# 7688A-kit-V2-1.net
KiCad netlist of a schematic drawn in Altium Designer
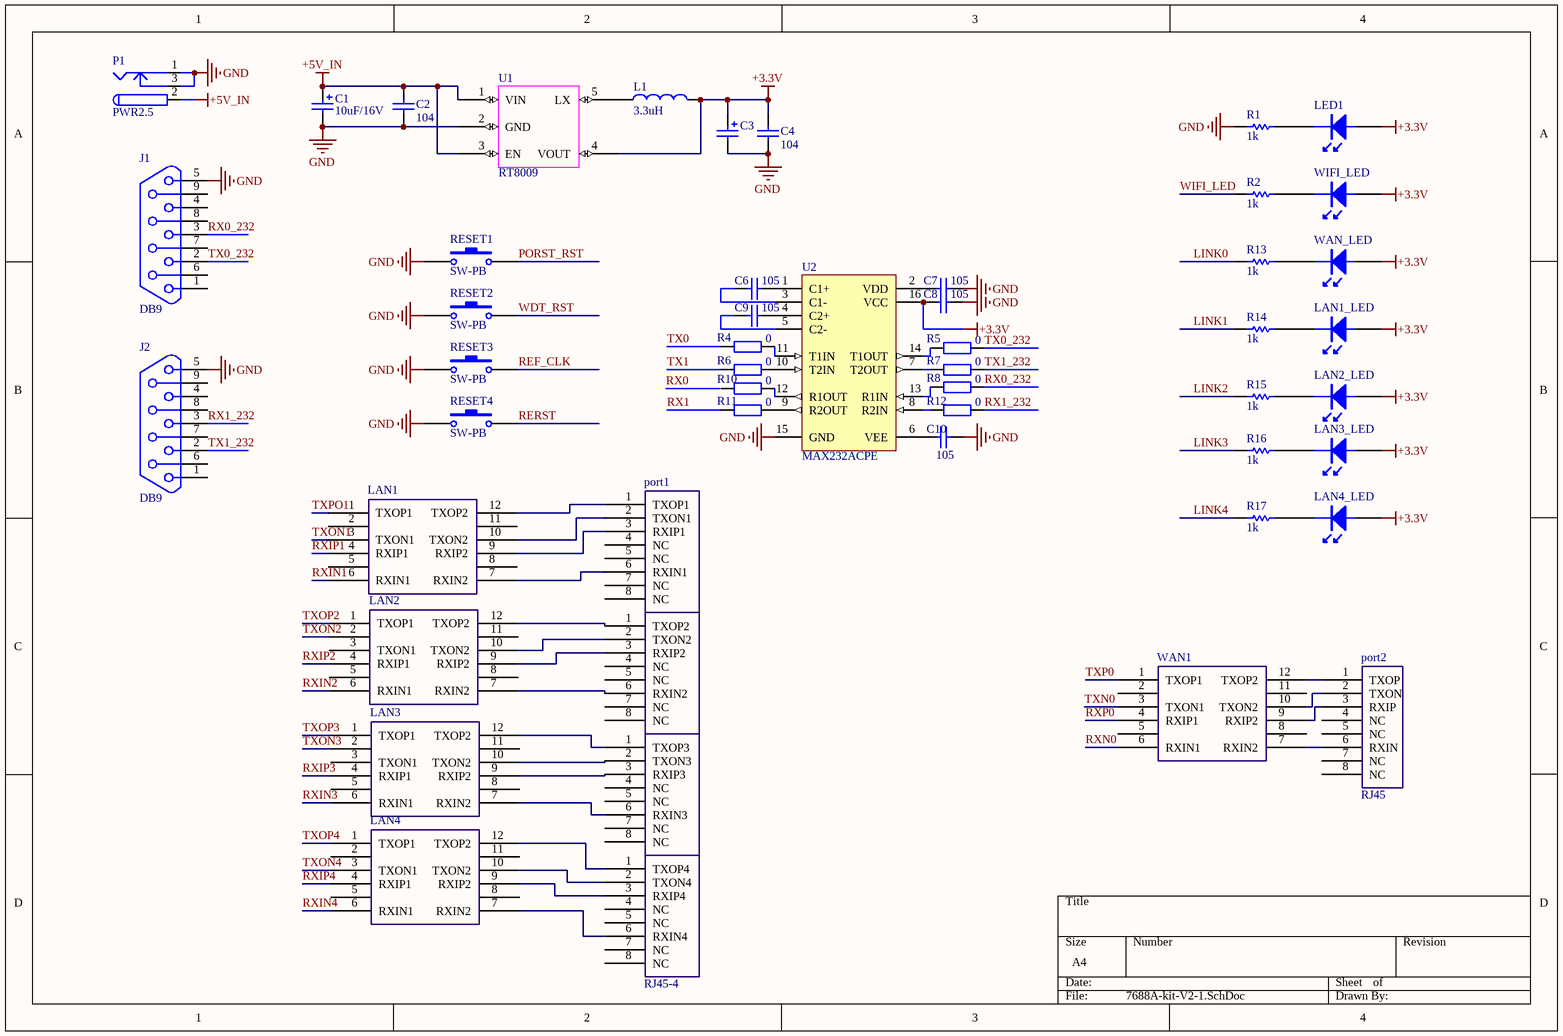
[diagram p0: 7688A-kit-V2-1.SchDoc]

(export (version "E")
  (design (tool "Eeschema 10.0.6"))
  (components
    (comp (ref "C1")
      (value "10uF/16V")
      (footprint "0805")
      (description "Polarized Capacitor (Surface Mount)")
      (fields
        (field (name "MANUFACTURER") "Generic Components")
        (field (name "PUBLISHER") "Altium Hobart Technology Centre")
      )
      (libsource (lib "*") (part "Cap Pol3"))
    )
    (comp (ref "C2")
      (value "104")
      (footprint "0603")
      (description "Capacitor")
      (fields
        (field (name "MANUFACTURER") "Generic Components")
        (field (name "PUBLISHER") "Altium Hobart Technology Centre")
      )
      (libsource (lib "*") (part "Cap"))
    )
    (comp (ref "C3")
      (value "10uF/16V")
      (footprint "0805")
      (description "Polarized Capacitor (Surface Mount)")
      (fields
        (field (name "MANUFACTURER") "Generic Components")
        (field (name "PUBLISHER") "Altium Hobart Technology Centre")
      )
      (libsource (lib "*") (part "Cap Pol3"))
    )
    (comp (ref "C4")
      (value "104")
      (footprint "0603")
      (description "Capacitor")
      (fields
        (field (name "MANUFACTURER") "Generic Components")
        (field (name "PUBLISHER") "Altium Hobart Technology Centre")
      )
      (libsource (lib "*") (part "Cap"))
    )
    (comp (ref "C6")
      (value "105")
      (footprint "0603")
      (description "Capacitor")
      (fields (field (name "PUBLISHER") "Altium Limited"))
      (libsource (lib "HLK-RM04_KIT-V2.3") (part "Cap"))
    )
    (comp (ref "C7")
      (value "105")
      (footprint "0603")
      (description "Capacitor")
      (fields (field (name "PUBLISHER") "Altium Limited"))
      (libsource (lib "HLK-RM04_KIT-V2.3") (part "Cap"))
    )
    (comp (ref "C8")
      (value "105")
      (footprint "0603")
      (description "Capacitor")
      (fields (field (name "PUBLISHER") "Altium Limited"))
      (libsource (lib "HLK-RM04_KIT-V2.3") (part "Cap"))
    )
    (comp (ref "C9")
      (value "105")
      (footprint "0603")
      (description "Capacitor")
      (fields (field (name "PUBLISHER") "Altium Limited"))
      (libsource (lib "HLK-RM04_KIT-V2.3") (part "Cap"))
    )
    (comp (ref "C10")
      (value "105")
      (footprint "0603")
      (description "Capacitor")
      (fields (field (name "PUBLISHER") "Altium Limited"))
      (libsource (lib "HLK-RM04_KIT-V2.3") (part "Cap"))
    )
    (comp (ref "J1") (value "DB9") (footprint "DB9s") (libsource (lib "HLK-RM04_KIT-V2.3") (part "DB9")))
    (comp (ref "J2") (value "DB9") (footprint "DB9s") (libsource (lib "HLK-RM04_KIT-V2.3") (part "DB9")))
    (comp (ref "L1") (value "3.3uH") (footprint "2520") (libsource (lib "ARM9") (part "INDUCTOR1")))
    (comp (ref "LAN1") (value "~") (footprint "tf-1016dg") (libsource (lib "TF-1016DG") (part "Component_1")))
    (comp (ref "LAN1_LED")
      (value "~")
      (footprint "0603LED")
      (libsource (lib "Miscellaneous Devices") (part "LED"))
    )
    (comp (ref "LAN2") (value "~") (footprint "tf-1016dg") (libsource (lib "TF-1016DG") (part "Component_1")))
    (comp (ref "LAN2_LED")
      (value "~")
      (footprint "0603LED")
      (libsource (lib "Miscellaneous Devices") (part "LED"))
    )
    (comp (ref "LAN3") (value "~") (footprint "tf-1016dg") (libsource (lib "TF-1016DG") (part "Component_1")))
    (comp (ref "LAN3_LED")
      (value "~")
      (footprint "0603LED")
      (libsource (lib "Miscellaneous Devices") (part "LED"))
    )
    (comp (ref "LAN4") (value "~") (footprint "tf-1016dg") (libsource (lib "TF-1016DG") (part "Component_1")))
    (comp (ref "LAN4_LED")
      (value "~")
      (footprint "0603LED")
      (libsource (lib "Miscellaneous Devices") (part "LED"))
    )
    (comp (ref "LED1")
      (value "~")
      (footprint "0603LED")
      (libsource (lib "Miscellaneous Devices") (part "LED"))
    )
    (comp (ref "P1")
      (value "PWR2.5")
      (footprint "HLK-M35-KIT-V2.1:POWER_STK1")
      (description "Low Voltage Power Supply Connector")
      (libsource (lib "HLK-RM04_KIT-V2.3") (part "PWR2.5"))
    )
    (comp (ref "port1") (value "RJ45-4") (footprint "RJ45-4") (libsource (lib "TF-1016DG") (part "RJ45-4")))
    (comp (ref "port2") (value "RJ45") (footprint "RJ45-8P8C") (libsource (lib "TF-1016DG") (part "RJ45")))
    (comp (ref "R1")
      (value "1k")
      (footprint "0603")
      (description "Resistor")
      (fields (field (name "Comment") "Res1") (field (name "PUBLISHER") "Altium Limited"))
      (libsource (lib "Miscellaneous Devices") (part "Res1"))
    )
    (comp (ref "R2")
      (value "1k")
      (footprint "0603")
      (description "Resistor")
      (fields (field (name "Comment") "Res1") (field (name "PUBLISHER") "Altium Limited"))
      (libsource (lib "Miscellaneous Devices") (part "Res1"))
    )
    (comp (ref "R4")
      (value "0")
      (footprint "0603")
      (description "Resistor")
      (fields (field (name "PUBLISHER") "Altium Limited"))
      (libsource (lib "HLK-RM04_KIT-V2.3") (part "Res2"))
    )
    (comp (ref "R5")
      (value "0")
      (footprint "0603")
      (description "Resistor")
      (fields (field (name "PUBLISHER") "Altium Limited"))
      (libsource (lib "HLK-RM04_KIT-V2.3") (part "Res2"))
    )
    (comp (ref "R6")
      (value "0")
      (footprint "0603")
      (description "Resistor")
      (fields (field (name "PUBLISHER") "Altium Limited"))
      (libsource (lib "HLK-RM04_KIT-V2.3") (part "Res2"))
    )
    (comp (ref "R7")
      (value "0")
      (footprint "0603")
      (description "Resistor")
      (fields (field (name "PUBLISHER") "Altium Limited"))
      (libsource (lib "HLK-RM04_KIT-V2.3") (part "Res2"))
    )
    (comp (ref "R8")
      (value "0")
      (footprint "0603")
      (description "Resistor")
      (fields (field (name "PUBLISHER") "Altium Limited"))
      (libsource (lib "HLK-RM04_KIT-V2.3") (part "Res2"))
    )
    (comp (ref "R10")
      (value "0")
      (footprint "0603")
      (description "Resistor")
      (fields (field (name "PUBLISHER") "Altium Limited"))
      (libsource (lib "HLK-RM04_KIT-V2.3") (part "Res2"))
    )
    (comp (ref "R11")
      (value "0")
      (footprint "0603")
      (description "Resistor")
      (fields (field (name "PUBLISHER") "Altium Limited"))
      (libsource (lib "HLK-RM04_KIT-V2.3") (part "Res2"))
    )
    (comp (ref "R12")
      (value "0")
      (footprint "0603")
      (description "Resistor")
      (fields (field (name "PUBLISHER") "Altium Limited"))
      (libsource (lib "HLK-RM04_KIT-V2.3") (part "Res2"))
    )
    (comp (ref "R13")
      (value "1k")
      (footprint "0603")
      (description "Resistor")
      (fields (field (name "Comment") "Res1") (field (name "PUBLISHER") "Altium Limited"))
      (libsource (lib "Miscellaneous Devices") (part "Res1"))
    )
    (comp (ref "R14")
      (value "1k")
      (footprint "0603")
      (description "Resistor")
      (fields (field (name "Comment") "Res1") (field (name "PUBLISHER") "Altium Limited"))
      (libsource (lib "Miscellaneous Devices") (part "Res1"))
    )
    (comp (ref "R15")
      (value "1k")
      (footprint "0603")
      (description "Resistor")
      (fields (field (name "Comment") "Res1") (field (name "PUBLISHER") "Altium Limited"))
      (libsource (lib "Miscellaneous Devices") (part "Res1"))
    )
    (comp (ref "R16")
      (value "1k")
      (footprint "0603")
      (description "Resistor")
      (fields (field (name "Comment") "Res1") (field (name "PUBLISHER") "Altium Limited"))
      (libsource (lib "Miscellaneous Devices") (part "Res1"))
    )
    (comp (ref "R17")
      (value "1k")
      (footprint "0603")
      (description "Resistor")
      (fields (field (name "Comment") "Res1") (field (name "PUBLISHER") "Altium Limited"))
      (libsource (lib "Miscellaneous Devices") (part "Res1"))
    )
    (comp (ref "RESET1")
      (value "SW-PB")
      (footprint "SWITCH")
      (description "Switch")
      (fields (field (name "PUBLISHER") "Altium Limited"))
      (libsource (lib "Miscellaneous Devices") (part "SW-PB"))
    )
    (comp (ref "RESET2")
      (value "SW-PB")
      (footprint "SWITCH")
      (description "Switch")
      (fields (field (name "PUBLISHER") "Altium Limited"))
      (libsource (lib "Miscellaneous Devices") (part "SW-PB"))
    )
    (comp (ref "RESET3")
      (value "SW-PB")
      (footprint "SWITCH")
      (description "Switch")
      (fields (field (name "PUBLISHER") "Altium Limited"))
      (libsource (lib "Miscellaneous Devices") (part "SW-PB"))
    )
    (comp (ref "RESET4")
      (value "SW-PB")
      (footprint "SWITCH")
      (description "Switch")
      (fields (field (name "PUBLISHER") "Altium Limited"))
      (libsource (lib "Miscellaneous Devices") (part "SW-PB"))
    )
    (comp (ref "U1")
      (value "RT8009")
      (footprint "HLK-M35-KIT-V2.1:SOT23-5")
      (libsource (lib "ARM9") (part "RT8009"))
    )
    (comp (ref "U2")
      (value "MAX232ACPE")
      (footprint "HLK-M35-KIT-V2.1:MAX3232")
      (description "+5V Powered, Multi-Channel RS-232 Driver/Receiver")
      (fields (field (name "PUBLISHER") "Altium Limited"))
      (libsource (lib "HLK-RM04_KIT-V2.3") (part "MAX232ACPE"))
    )
    (comp (ref "WAN1") (value "~") (footprint "tf-1016dg") (libsource (lib "TF-1016DG") (part "Component_1")))
    (comp (ref "WAN_LED")
      (value "~")
      (footprint "0603LED")
      (libsource (lib "Miscellaneous Devices") (part "LED"))
    )
    (comp (ref "WIFI_LED")
      (value "~")
      (footprint "0603LED")
      (libsource (lib "Miscellaneous Devices") (part "LED"))
    )
  )
  (nets
    (net (code "1") (name "+3.3V") (class "Default")
      (node (ref "C3") (pin "1") (pinfunction "1_1") (pintype "passive"))
      (node (ref "C4") (pin "2") (pinfunction "2_2") (pintype "passive"))
      (node (ref "C8") (pin "1") (pinfunction "1_1") (pintype "passive"))
      (node (ref "L1") (pin "2") (pinfunction "2_2") (pintype "passive"))
      (node (ref "LAN1_LED") (pin "1") (pinfunction "1_1") (pintype "passive"))
      (node (ref "LAN2_LED") (pin "1") (pinfunction "1_1") (pintype "passive"))
      (node (ref "LAN3_LED") (pin "1") (pinfunction "1_1") (pintype "passive"))
      (node (ref "LAN4_LED") (pin "1") (pinfunction "1_1") (pintype "passive"))
      (node (ref "LED1") (pin "1") (pinfunction "1_1") (pintype "passive"))
      (node (ref "U1") (pin "4") (pinfunction "VOUT_4") (pintype "bidirectional"))
      (node (ref "U2") (pin "16") (pinfunction "VCC_16") (pintype "power_in"))
      (node (ref "WAN_LED") (pin "1") (pinfunction "1_1") (pintype "passive"))
      (node (ref "WIFI_LED") (pin "1") (pinfunction "1_1") (pintype "passive"))
    )
    (net (code "2") (name "+5V_IN") (class "Default")
      (node (ref "C1") (pin "1") (pinfunction "1_1") (pintype "passive"))
      (node (ref "C2") (pin "2") (pinfunction "2_2") (pintype "passive"))
      (node (ref "P1") (pin "2") (pinfunction "2_2") (pintype "power_in"))
      (node (ref "U1") (pin "1") (pinfunction "VIN_1") (pintype "bidirectional"))
      (node (ref "U1") (pin "3") (pinfunction "EN_3") (pintype "bidirectional"))
    )
    (net (code "3") (name "/LINK0") (class "Default")
      (node (ref "R13") (pin "2") (pinfunction "2_2") (pintype "passive"))
    )
    (net (code "4") (name "/LINK1") (class "Default")
      (node (ref "R14") (pin "2") (pinfunction "2_2") (pintype "passive"))
    )
    (net (code "5") (name "/LINK2") (class "Default")
      (node (ref "R15") (pin "2") (pinfunction "2_2") (pintype "passive"))
    )
    (net (code "6") (name "/LINK3") (class "Default")
      (node (ref "R16") (pin "2") (pinfunction "2_2") (pintype "passive"))
    )
    (net (code "7") (name "/LINK4") (class "Default")
      (node (ref "R17") (pin "2") (pinfunction "2_2") (pintype "passive"))
    )
    (net (code "8") (name "/PORST_RST") (class "Default")
      (node (ref "RESET1") (pin "2") (pinfunction "2_2") (pintype "passive"))
    )
    (net (code "9") (name "/REF_CLK") (class "Default")
      (node (ref "RESET3") (pin "2") (pinfunction "2_2") (pintype "passive"))
    )
    (net (code "10") (name "/RERST") (class "Default")
      (node (ref "RESET4") (pin "2") (pinfunction "2_2") (pintype "passive"))
    )
    (net (code "12") (name "/RX0_232") (class "Default")
      (node (ref "J1") (pin "3") (pinfunction "3_3") (pintype "passive"))
      (node (ref "R8") (pin "2") (pinfunction "2_2") (pintype "passive"))
    )
    (net (code "13") (name "/RX1") (class "Default")
      (node (ref "R11") (pin "1") (pinfunction "1_1") (pintype "passive"))
    )
    (net (code "14") (name "/RX1_232") (class "Default")
      (node (ref "J2") (pin "3") (pinfunction "3_3") (pintype "passive"))
      (node (ref "R12") (pin "2") (pinfunction "2_2") (pintype "passive"))
    )
    (net (code "15") (name "/RXIN1") (class "Default")
      (node (ref "LAN1") (pin "6") (pinfunction "RXIN1_6") (pintype "passive"))
    )
    (net (code "16") (name "/RXIN2") (class "Default")
      (node (ref "LAN2") (pin "6") (pinfunction "RXIN1_6") (pintype "passive"))
    )
    (net (code "17") (name "/RXIN3") (class "Default")
      (node (ref "LAN3") (pin "6") (pinfunction "RXIN1_6") (pintype "passive"))
    )
    (net (code "18") (name "/RXIN4") (class "Default")
      (node (ref "LAN4") (pin "6") (pinfunction "RXIN1_6") (pintype "passive"))
    )
    (net (code "19") (name "/RXIP1") (class "Default")
      (node (ref "LAN1") (pin "4") (pinfunction "RXIP1_4") (pintype "passive"))
    )
    (net (code "20") (name "/RXIP2") (class "Default")
      (node (ref "LAN2") (pin "4") (pinfunction "RXIP1_4") (pintype "passive"))
    )
    (net (code "21") (name "/RXIP3") (class "Default")
      (node (ref "LAN3") (pin "4") (pinfunction "RXIP1_4") (pintype "passive"))
    )
    (net (code "22") (name "/RXIP4") (class "Default")
      (node (ref "LAN4") (pin "4") (pinfunction "RXIP1_4") (pintype "passive"))
    )
    (net (code "23") (name "/RXN0") (class "Default")
      (node (ref "WAN1") (pin "6") (pinfunction "RXIN1_6") (pintype "passive"))
    )
    (net (code "24") (name "/RXP0") (class "Default")
      (node (ref "WAN1") (pin "4") (pinfunction "RXIP1_4") (pintype "passive"))
    )
    (net (code "25") (name "/TX0") (class "Default")
      (node (ref "R4") (pin "1") (pinfunction "1_1") (pintype "passive"))
    )
    (net (code "26") (name "/TX0_232") (class "Default")
      (node (ref "J1") (pin "2") (pinfunction "2_2") (pintype "passive"))
      (node (ref "R5") (pin "2") (pinfunction "2_2") (pintype "passive"))
    )
    (net (code "27") (name "/TX1") (class "Default")
      (node (ref "R6") (pin "1") (pinfunction "1_1") (pintype "passive"))
    )
    (net (code "28") (name "/TX1_232") (class "Default")
      (node (ref "J2") (pin "2") (pinfunction "2_2") (pintype "passive"))
      (node (ref "R7") (pin "2") (pinfunction "2_2") (pintype "passive"))
    )
    (net (code "29") (name "/TXN0") (class "Default")
      (node (ref "WAN1") (pin "3") (pinfunction "TXON1_3") (pintype "passive"))
    )
    (net (code "30") (name "/TXON1") (class "Default")
      (node (ref "LAN1") (pin "3") (pinfunction "TXON1_3") (pintype "passive"))
    )
    (net (code "31") (name "/TXON2") (class "Default") (node (ref "LAN2") (pin "2") (pintype "passive")))
    (net (code "32") (name "/TXON3") (class "Default") (node (ref "LAN3") (pin "2") (pintype "passive")))
    (net (code "33") (name "/TXON4") (class "Default")
      (node (ref "LAN4") (pin "3") (pinfunction "TXON1_3") (pintype "passive"))
    )
    (net (code "34") (name "/TXOP2") (class "Default")
      (node (ref "LAN2") (pin "1") (pinfunction "TXOP1_1") (pintype "passive"))
    )
    (net (code "35") (name "/TXOP3") (class "Default")
      (node (ref "LAN3") (pin "1") (pinfunction "TXOP1_1") (pintype "passive"))
    )
    (net (code "36") (name "/TXOP4") (class "Default")
      (node (ref "LAN4") (pin "1") (pinfunction "TXOP1_1") (pintype "passive"))
    )
    (net (code "37") (name "/TXP0") (class "Default")
      (node (ref "WAN1") (pin "1") (pinfunction "TXOP1_1") (pintype "passive"))
    )
    (net (code "38") (name "/TXPO1") (class "Default")
      (node (ref "LAN1") (pin "1") (pinfunction "TXOP1_1") (pintype "passive"))
    )
    (net (code "39") (name "/WDT_RST") (class "Default")
      (node (ref "RESET2") (pin "2") (pinfunction "2_2") (pintype "passive"))
    )
    (net (code "40") (name "/WIFI_LED") (class "Default")
      (node (ref "R2") (pin "2") (pinfunction "2_2") (pintype "passive"))
    )
    (net (code "41") (name "GND") (class "Default")
      (node (ref "C1") (pin "2") (pinfunction "2_2") (pintype "passive"))
      (node (ref "C10") (pin "1") (pinfunction "1_1") (pintype "passive"))
      (node (ref "C2") (pin "1") (pinfunction "1_1") (pintype "passive"))
      (node (ref "C3") (pin "2") (pinfunction "2_2") (pintype "passive"))
      (node (ref "C4") (pin "1") (pinfunction "1_1") (pintype "passive"))
      (node (ref "C7") (pin "2") (pinfunction "2_2") (pintype "passive"))
      (node (ref "C8") (pin "2") (pinfunction "2_2") (pintype "passive"))
      (node (ref "J1") (pin "5") (pinfunction "5_5") (pintype "passive"))
      (node (ref "J2") (pin "5") (pinfunction "5_5") (pintype "passive"))
      (node (ref "P1") (pin "1") (pinfunction "1_1") (pintype "power_in"))
      (node (ref "P1") (pin "3") (pinfunction "3_3") (pintype "power_in"))
      (node (ref "R1") (pin "2") (pinfunction "2_2") (pintype "passive"))
      (node (ref "RESET1") (pin "1") (pinfunction "1_1") (pintype "passive"))
      (node (ref "RESET2") (pin "1") (pinfunction "1_1") (pintype "passive"))
      (node (ref "RESET3") (pin "1") (pinfunction "1_1") (pintype "passive"))
      (node (ref "RESET4") (pin "1") (pinfunction "1_1") (pintype "passive"))
      (node (ref "U1") (pin "2") (pinfunction "GND_2") (pintype "bidirectional"))
      (node (ref "U2") (pin "15") (pinfunction "GND_15") (pintype "power_in"))
    )
    (net (code "42") (name "Net-(LAN1-RXIN2)") (class "Default")
      (node (ref "LAN1") (pin "7") (pinfunction "RXIN2_7") (pintype "passive"))
      (node (ref "port1") (pin "6") (pinfunction "RXIN1_6") (pintype "passive"))
    )
    (net (code "43") (name "Net-(LAN1-RXIP2)") (class "Default")
      (node (ref "LAN1") (pin "9") (pinfunction "RXIP2_9") (pintype "passive"))
      (node (ref "port1") (pin "3") (pinfunction "RXIP1_3") (pintype "passive"))
    )
    (net (code "44") (name "Net-(LAN1-TXON2)") (class "Default")
      (node (ref "LAN1") (pin "10") (pinfunction "TXON2_10") (pintype "passive"))
      (node (ref "port1") (pin "2") (pinfunction "TXON1_2") (pintype "passive"))
    )
    (net (code "45") (name "Net-(LAN1-TXOP2)") (class "Default")
      (node (ref "LAN1") (pin "12") (pinfunction "TXOP2_12") (pintype "passive"))
      (node (ref "port1") (pin "1") (pinfunction "TXOP1_1") (pintype "passive"))
    )
    (net (code "46") (name "Net-(LAN1_LED-Pad2)") (class "Default")
      (node (ref "LAN1_LED") (pin "2") (pinfunction "2_2") (pintype "passive"))
      (node (ref "R14") (pin "1") (pinfunction "1_1") (pintype "passive"))
    )
    (net (code "47") (name "Net-(LAN2-RXIN2)") (class "Default")
      (node (ref "LAN2") (pin "7") (pinfunction "RXIN2_7") (pintype "passive"))
      (node (ref "port1") (pin "6") (pinfunction "RXIN2_6") (pintype "passive"))
    )
    (net (code "48") (name "Net-(LAN2-RXIP2)") (class "Default")
      (node (ref "LAN2") (pin "9") (pinfunction "RXIP2_9") (pintype "passive"))
      (node (ref "port1") (pin "3") (pinfunction "RXIP2_3") (pintype "passive"))
    )
    (net (code "49") (name "Net-(LAN2-TXON2)") (class "Default")
      (node (ref "LAN2") (pin "10") (pinfunction "TXON2_10") (pintype "passive"))
      (node (ref "port1") (pin "2") (pinfunction "TXON2_2") (pintype "passive"))
    )
    (net (code "50") (name "Net-(LAN2-TXOP2)") (class "Default")
      (node (ref "LAN2") (pin "12") (pinfunction "TXOP2_12") (pintype "passive"))
      (node (ref "port1") (pin "1") (pinfunction "TXOP2_1") (pintype "passive"))
    )
    (net (code "51") (name "Net-(LAN2_LED-Pad2)") (class "Default")
      (node (ref "LAN2_LED") (pin "2") (pinfunction "2_2") (pintype "passive"))
      (node (ref "R15") (pin "1") (pinfunction "1_1") (pintype "passive"))
    )
    (net (code "52") (name "Net-(LAN3-RXIN2)") (class "Default")
      (node (ref "LAN3") (pin "7") (pinfunction "RXIN2_7") (pintype "passive"))
      (node (ref "port1") (pin "6") (pinfunction "RXIN3_6") (pintype "passive"))
    )
    (net (code "53") (name "Net-(LAN3-RXIP2)") (class "Default")
      (node (ref "LAN3") (pin "9") (pinfunction "RXIP2_9") (pintype "passive"))
      (node (ref "port1") (pin "3") (pinfunction "RXIP3_3") (pintype "passive"))
    )
    (net (code "54") (name "Net-(LAN3-TXON2)") (class "Default")
      (node (ref "LAN3") (pin "10") (pinfunction "TXON2_10") (pintype "passive"))
      (node (ref "port1") (pin "2") (pinfunction "TXON3_2") (pintype "passive"))
    )
    (net (code "55") (name "Net-(LAN3-TXOP2)") (class "Default")
      (node (ref "LAN3") (pin "12") (pinfunction "TXOP2_12") (pintype "passive"))
      (node (ref "port1") (pin "1") (pinfunction "TXOP3_1") (pintype "passive"))
    )
    (net (code "56") (name "Net-(LAN3_LED-Pad2)") (class "Default")
      (node (ref "LAN3_LED") (pin "2") (pinfunction "2_2") (pintype "passive"))
      (node (ref "R16") (pin "1") (pinfunction "1_1") (pintype "passive"))
    )
    (net (code "57") (name "Net-(LAN4-RXIN2)") (class "Default")
      (node (ref "LAN4") (pin "7") (pinfunction "RXIN2_7") (pintype "passive"))
      (node (ref "port1") (pin "6") (pinfunction "RXIN4_6") (pintype "passive"))
    )
    (net (code "58") (name "Net-(LAN4-RXIP2)") (class "Default")
      (node (ref "LAN4") (pin "9") (pinfunction "RXIP2_9") (pintype "passive"))
      (node (ref "port1") (pin "3") (pinfunction "RXIP4_3") (pintype "passive"))
    )
    (net (code "59") (name "Net-(LAN4-TXON2)") (class "Default")
      (node (ref "LAN4") (pin "10") (pinfunction "TXON2_10") (pintype "passive"))
      (node (ref "port1") (pin "2") (pinfunction "TXON4_2") (pintype "passive"))
    )
    (net (code "60") (name "Net-(LAN4-TXOP2)") (class "Default")
      (node (ref "LAN4") (pin "12") (pinfunction "TXOP2_12") (pintype "passive"))
      (node (ref "port1") (pin "1") (pinfunction "TXOP4_1") (pintype "passive"))
    )
    (net (code "61") (name "Net-(LAN4_LED-Pad2)") (class "Default")
      (node (ref "LAN4_LED") (pin "2") (pinfunction "2_2") (pintype "passive"))
      (node (ref "R17") (pin "1") (pinfunction "1_1") (pintype "passive"))
    )
    (net (code "62") (name "Net-(LED1-Pad2)") (class "Default")
      (node (ref "LED1") (pin "2") (pinfunction "2_2") (pintype "passive"))
      (node (ref "R1") (pin "1") (pinfunction "1_1") (pintype "passive"))
    )
    (net (code "63") (name "Net-(R2-Pad1)") (class "Default")
      (node (ref "R2") (pin "1") (pinfunction "1_1") (pintype "passive"))
      (node (ref "WIFI_LED") (pin "2") (pinfunction "2_2") (pintype "passive"))
    )
    (net (code "64") (name "Net-(R13-Pad1)") (class "Default")
      (node (ref "R13") (pin "1") (pinfunction "1_1") (pintype "passive"))
      (node (ref "WAN_LED") (pin "2") (pinfunction "2_2") (pintype "passive"))
    )
    (net (code "65") (name "Net-(U1-LX)") (class "Default")
      (node (ref "L1") (pin "1") (pinfunction "1_1") (pintype "passive"))
      (node (ref "U1") (pin "5") (pinfunction "LX_5") (pintype "bidirectional"))
    )
    (net (code "66") (name "Net-(U2-C1+)") (class "Default")
      (node (ref "C6") (pin "2") (pinfunction "2_2") (pintype "passive"))
      (node (ref "U2") (pin "1") (pinfunction "C1+_1") (pintype "passive"))
    )
    (net (code "67") (name "Net-(U2-C1-)") (class "Default")
      (node (ref "C6") (pin "1") (pinfunction "1_1") (pintype "passive"))
      (node (ref "U2") (pin "3") (pinfunction "C1-_3") (pintype "passive"))
    )
    (net (code "68") (name "Net-(U2-C2+)") (class "Default")
      (node (ref "C9") (pin "2") (pinfunction "2_2") (pintype "passive"))
      (node (ref "U2") (pin "4") (pinfunction "C2+_4") (pintype "passive"))
    )
    (net (code "69") (name "Net-(U2-C2-)") (class "Default")
      (node (ref "C9") (pin "1") (pinfunction "1_1") (pintype "passive"))
      (node (ref "U2") (pin "5") (pinfunction "C2-_5") (pintype "passive"))
    )
    (net (code "70") (name "Net-(U2-R1IN)") (class "Default")
      (node (ref "R8") (pin "1") (pinfunction "1_1") (pintype "passive"))
      (node (ref "U2") (pin "13") (pinfunction "R1IN_13") (pintype "input"))
    )
    (net (code "71") (name "Net-(U2-R1OUT)") (class "Default")
      (node (ref "R10") (pin "2") (pinfunction "2_2") (pintype "passive"))
      (node (ref "U2") (pin "12") (pinfunction "R1OUT_12") (pintype "output"))
    )
    (net (code "72") (name "Net-(U2-R2IN)") (class "Default")
      (node (ref "R12") (pin "1") (pinfunction "1_1") (pintype "passive"))
      (node (ref "U2") (pin "8") (pinfunction "R2IN_8") (pintype "input"))
    )
    (net (code "73") (name "Net-(U2-R2OUT)") (class "Default")
      (node (ref "R11") (pin "2") (pinfunction "2_2") (pintype "passive"))
      (node (ref "U2") (pin "9") (pinfunction "R2OUT_9") (pintype "output"))
    )
    (net (code "74") (name "Net-(U2-T1IN)") (class "Default")
      (node (ref "R4") (pin "2") (pinfunction "2_2") (pintype "passive"))
      (node (ref "U2") (pin "11") (pinfunction "T1IN_11") (pintype "input"))
    )
    (net (code "75") (name "Net-(U2-T1OUT)") (class "Default")
      (node (ref "R5") (pin "1") (pinfunction "1_1") (pintype "passive"))
      (node (ref "U2") (pin "14") (pinfunction "T1OUT_14") (pintype "output"))
    )
    (net (code "76") (name "Net-(U2-T2IN)") (class "Default")
      (node (ref "R6") (pin "2") (pinfunction "2_2") (pintype "passive"))
      (node (ref "U2") (pin "10") (pinfunction "T2IN_10") (pintype "input"))
    )
    (net (code "77") (name "Net-(U2-T2OUT)") (class "Default")
      (node (ref "R7") (pin "1") (pinfunction "1_1") (pintype "passive"))
      (node (ref "U2") (pin "7") (pinfunction "T2OUT_7") (pintype "output"))
    )
    (net (code "78") (name "Net-(U2-VDD)") (class "Default")
      (node (ref "C7") (pin "1") (pinfunction "1_1") (pintype "passive"))
      (node (ref "U2") (pin "2") (pinfunction "VDD_2") (pintype "power_in"))
    )
    (net (code "79") (name "Net-(U2-VEE)") (class "Default")
      (node (ref "C10") (pin "2") (pinfunction "2_2") (pintype "passive"))
      (node (ref "U2") (pin "6") (pinfunction "VEE_6") (pintype "power_in"))
    )
    (net (code "80") (name "Net-(WAN1-RXIN2)") (class "Default")
      (node (ref "WAN1") (pin "7") (pinfunction "RXIN2_7") (pintype "passive"))
      (node (ref "port2") (pin "6") (pinfunction "RXIN_6") (pintype "passive"))
    )
    (net (code "81") (name "Net-(WAN1-RXIP2)") (class "Default")
      (node (ref "WAN1") (pin "9") (pinfunction "RXIP2_9") (pintype "passive"))
      (node (ref "port2") (pin "3") (pinfunction "RXIP_3") (pintype "passive"))
    )
    (net (code "82") (name "Net-(WAN1-TXON2)") (class "Default")
      (node (ref "WAN1") (pin "10") (pinfunction "TXON2_10") (pintype "passive"))
      (node (ref "port2") (pin "2") (pinfunction "TXON_2") (pintype "passive"))
    )
    (net (code "83") (name "Net-(WAN1-TXOP2)") (class "Default")
      (node (ref "WAN1") (pin "12") (pinfunction "TXOP2_12") (pintype "passive"))
      (node (ref "port2") (pin "1") (pinfunction "TXOP_1") (pintype "passive"))
    )
    (net (code "84") (name "unconnected-(J1-Pad1)") (class "Default")
      (node (ref "J1") (pin "1") (pinfunction "1_1") (pintype "passive"))
    )
    (net (code "85") (name "unconnected-(J1-Pad4)") (class "Default")
      (node (ref "J1") (pin "4") (pinfunction "4_4") (pintype "passive"))
    )
    (net (code "86") (name "unconnected-(J1-Pad6)") (class "Default")
      (node (ref "J1") (pin "6") (pinfunction "6_6") (pintype "passive"))
    )
    (net (code "87") (name "unconnected-(J1-Pad7)") (class "Default")
      (node (ref "J1") (pin "7") (pinfunction "7_7") (pintype "passive"))
    )
    (net (code "88") (name "unconnected-(J1-Pad8)") (class "Default")
      (node (ref "J1") (pin "8") (pinfunction "8_8") (pintype "passive"))
    )
    (net (code "89") (name "unconnected-(J1-Pad9)") (class "Default")
      (node (ref "J1") (pin "9") (pinfunction "9_9") (pintype "passive"))
    )
    (net (code "90") (name "unconnected-(J2-Pad1)") (class "Default")
      (node (ref "J2") (pin "1") (pinfunction "1_1") (pintype "passive"))
    )
    (net (code "91") (name "unconnected-(J2-Pad4)") (class "Default")
      (node (ref "J2") (pin "4") (pinfunction "4_4") (pintype "passive"))
    )
    (net (code "92") (name "unconnected-(J2-Pad6)") (class "Default")
      (node (ref "J2") (pin "6") (pinfunction "6_6") (pintype "passive"))
    )
    (net (code "93") (name "unconnected-(J2-Pad7)") (class "Default")
      (node (ref "J2") (pin "7") (pinfunction "7_7") (pintype "passive"))
    )
    (net (code "94") (name "unconnected-(J2-Pad8)") (class "Default")
      (node (ref "J2") (pin "8") (pinfunction "8_8") (pintype "passive"))
    )
    (net (code "95") (name "unconnected-(J2-Pad9)") (class "Default")
      (node (ref "J2") (pin "9") (pinfunction "9_9") (pintype "passive"))
    )
    (net (code "96") (name "unconnected-(LAN1-Pad2)") (class "Default")
      (node (ref "LAN1") (pin "2") (pintype "passive"))
    )
    (net (code "97") (name "unconnected-(LAN1-Pad5)") (class "Default")
      (node (ref "LAN1") (pin "5") (pintype "passive"))
    )
    (net (code "98") (name "unconnected-(LAN1-Pad8)") (class "Default")
      (node (ref "LAN1") (pin "8") (pintype "passive"))
    )
    (net (code "99") (name "unconnected-(LAN1-Pad11)") (class "Default")
      (node (ref "LAN1") (pin "11") (pintype "passive"))
    )
    (net (code "100") (name "unconnected-(LAN2-Pad5)") (class "Default")
      (node (ref "LAN2") (pin "5") (pintype "passive"))
    )
    (net (code "101") (name "unconnected-(LAN2-Pad8)") (class "Default")
      (node (ref "LAN2") (pin "8") (pintype "passive"))
    )
    (net (code "102") (name "unconnected-(LAN2-Pad11)") (class "Default")
      (node (ref "LAN2") (pin "11") (pintype "passive"))
    )
    (net (code "103") (name "unconnected-(LAN2-TXON1-Pad3)") (class "Default")
      (node (ref "LAN2") (pin "3") (pinfunction "TXON1_3") (pintype "passive"))
    )
    (net (code "104") (name "unconnected-(LAN3-Pad5)") (class "Default")
      (node (ref "LAN3") (pin "5") (pintype "passive"))
    )
    (net (code "105") (name "unconnected-(LAN3-Pad8)") (class "Default")
      (node (ref "LAN3") (pin "8") (pintype "passive"))
    )
    (net (code "106") (name "unconnected-(LAN3-Pad11)") (class "Default")
      (node (ref "LAN3") (pin "11") (pintype "passive"))
    )
    (net (code "107") (name "unconnected-(LAN3-TXON1-Pad3)") (class "Default")
      (node (ref "LAN3") (pin "3") (pinfunction "TXON1_3") (pintype "passive"))
    )
    (net (code "108") (name "unconnected-(LAN4-Pad2)") (class "Default")
      (node (ref "LAN4") (pin "2") (pintype "passive"))
    )
    (net (code "109") (name "unconnected-(LAN4-Pad5)") (class "Default")
      (node (ref "LAN4") (pin "5") (pintype "passive"))
    )
    (net (code "110") (name "unconnected-(LAN4-Pad8)") (class "Default")
      (node (ref "LAN4") (pin "8") (pintype "passive"))
    )
    (net (code "111") (name "unconnected-(LAN4-Pad11)") (class "Default")
      (node (ref "LAN4") (pin "11") (pintype "passive"))
    )
    (net (code "112") (name "unconnected-(R10-Pad1)") (class "Default")
      (node (ref "R10") (pin "1") (pinfunction "1_1") (pintype "passive"))
    )
    (net (code "113") (name "unconnected-(WAN1-Pad2)") (class "Default")
      (node (ref "WAN1") (pin "2") (pintype "passive"))
    )
    (net (code "114") (name "unconnected-(WAN1-Pad5)") (class "Default")
      (node (ref "WAN1") (pin "5") (pintype "passive"))
    )
    (net (code "115") (name "unconnected-(WAN1-Pad8)") (class "Default")
      (node (ref "WAN1") (pin "8") (pintype "passive"))
    )
    (net (code "116") (name "unconnected-(WAN1-Pad11)") (class "Default")
      (node (ref "WAN1") (pin "11") (pintype "passive"))
    )
    (net (code "117") (name "unconnected-(port1-NC-Pad4)") (class "Default")
      (node (ref "port1") (pin "4") (pinfunction "NC_4") (pintype "passive"))
    )
    (net (code "118") (name "unconnected-(port1-NC-Pad4)_1") (class "Default")
      (node (ref "port1") (pin "4") (pinfunction "NC_4") (pintype "passive"))
    )
    (net (code "119") (name "unconnected-(port1-NC-Pad4)_2") (class "Default")
      (node (ref "port1") (pin "4") (pinfunction "NC_4") (pintype "passive"))
    )
    (net (code "120") (name "unconnected-(port1-NC-Pad4)_3") (class "Default")
      (node (ref "port1") (pin "4") (pinfunction "NC_4") (pintype "passive"))
    )
    (net (code "121") (name "unconnected-(port1-NC-Pad5)") (class "Default")
      (node (ref "port1") (pin "5") (pinfunction "NC_5") (pintype "passive"))
    )
    (net (code "122") (name "unconnected-(port1-NC-Pad5)_1") (class "Default")
      (node (ref "port1") (pin "5") (pinfunction "NC_5") (pintype "passive"))
    )
    (net (code "123") (name "unconnected-(port1-NC-Pad5)_2") (class "Default")
      (node (ref "port1") (pin "5") (pinfunction "NC_5") (pintype "passive"))
    )
    (net (code "124") (name "unconnected-(port1-NC-Pad5)_3") (class "Default")
      (node (ref "port1") (pin "5") (pinfunction "NC_5") (pintype "passive"))
    )
    (net (code "125") (name "unconnected-(port1-NC-Pad7)") (class "Default")
      (node (ref "port1") (pin "7") (pinfunction "NC_7") (pintype "passive"))
    )
    (net (code "126") (name "unconnected-(port1-NC-Pad7)_1") (class "Default")
      (node (ref "port1") (pin "7") (pinfunction "NC_7") (pintype "passive"))
    )
    (net (code "127") (name "unconnected-(port1-NC-Pad7)_2") (class "Default")
      (node (ref "port1") (pin "7") (pinfunction "NC_7") (pintype "passive"))
    )
    (net (code "128") (name "unconnected-(port1-NC-Pad7)_3") (class "Default")
      (node (ref "port1") (pin "7") (pinfunction "NC_7") (pintype "passive"))
    )
    (net (code "129") (name "unconnected-(port1-NC-Pad8)") (class "Default")
      (node (ref "port1") (pin "8") (pinfunction "NC_8") (pintype "passive"))
    )
    (net (code "130") (name "unconnected-(port1-NC-Pad8)_1") (class "Default")
      (node (ref "port1") (pin "8") (pinfunction "NC_8") (pintype "passive"))
    )
    (net (code "131") (name "unconnected-(port1-NC-Pad8)_2") (class "Default")
      (node (ref "port1") (pin "8") (pinfunction "NC_8") (pintype "passive"))
    )
    (net (code "132") (name "unconnected-(port1-NC-Pad8)_3") (class "Default")
      (node (ref "port1") (pin "8") (pinfunction "NC_8") (pintype "passive"))
    )
    (net (code "133") (name "unconnected-(port2-NC-Pad4)") (class "Default")
      (node (ref "port2") (pin "4") (pinfunction "NC_4") (pintype "passive"))
    )
    (net (code "134") (name "unconnected-(port2-NC-Pad5)") (class "Default")
      (node (ref "port2") (pin "5") (pinfunction "NC_5") (pintype "passive"))
    )
    (net (code "135") (name "unconnected-(port2-NC-Pad7)") (class "Default")
      (node (ref "port2") (pin "7") (pinfunction "NC_7") (pintype "passive"))
    )
    (net (code "136") (name "unconnected-(port2-NC-Pad8)") (class "Default")
      (node (ref "port2") (pin "8") (pinfunction "NC_8") (pintype "passive"))
    )
  )
)
